# RaspiPowerHat.net
KiCad netlist of a schematic drawn in EAGLE
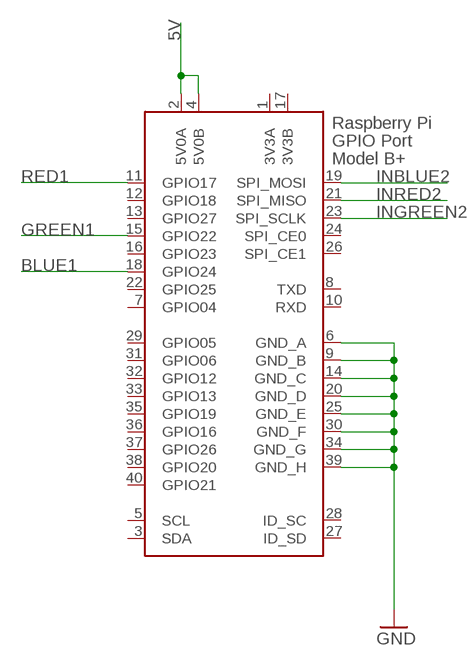
[diagram p0: schematic, sheet 1]
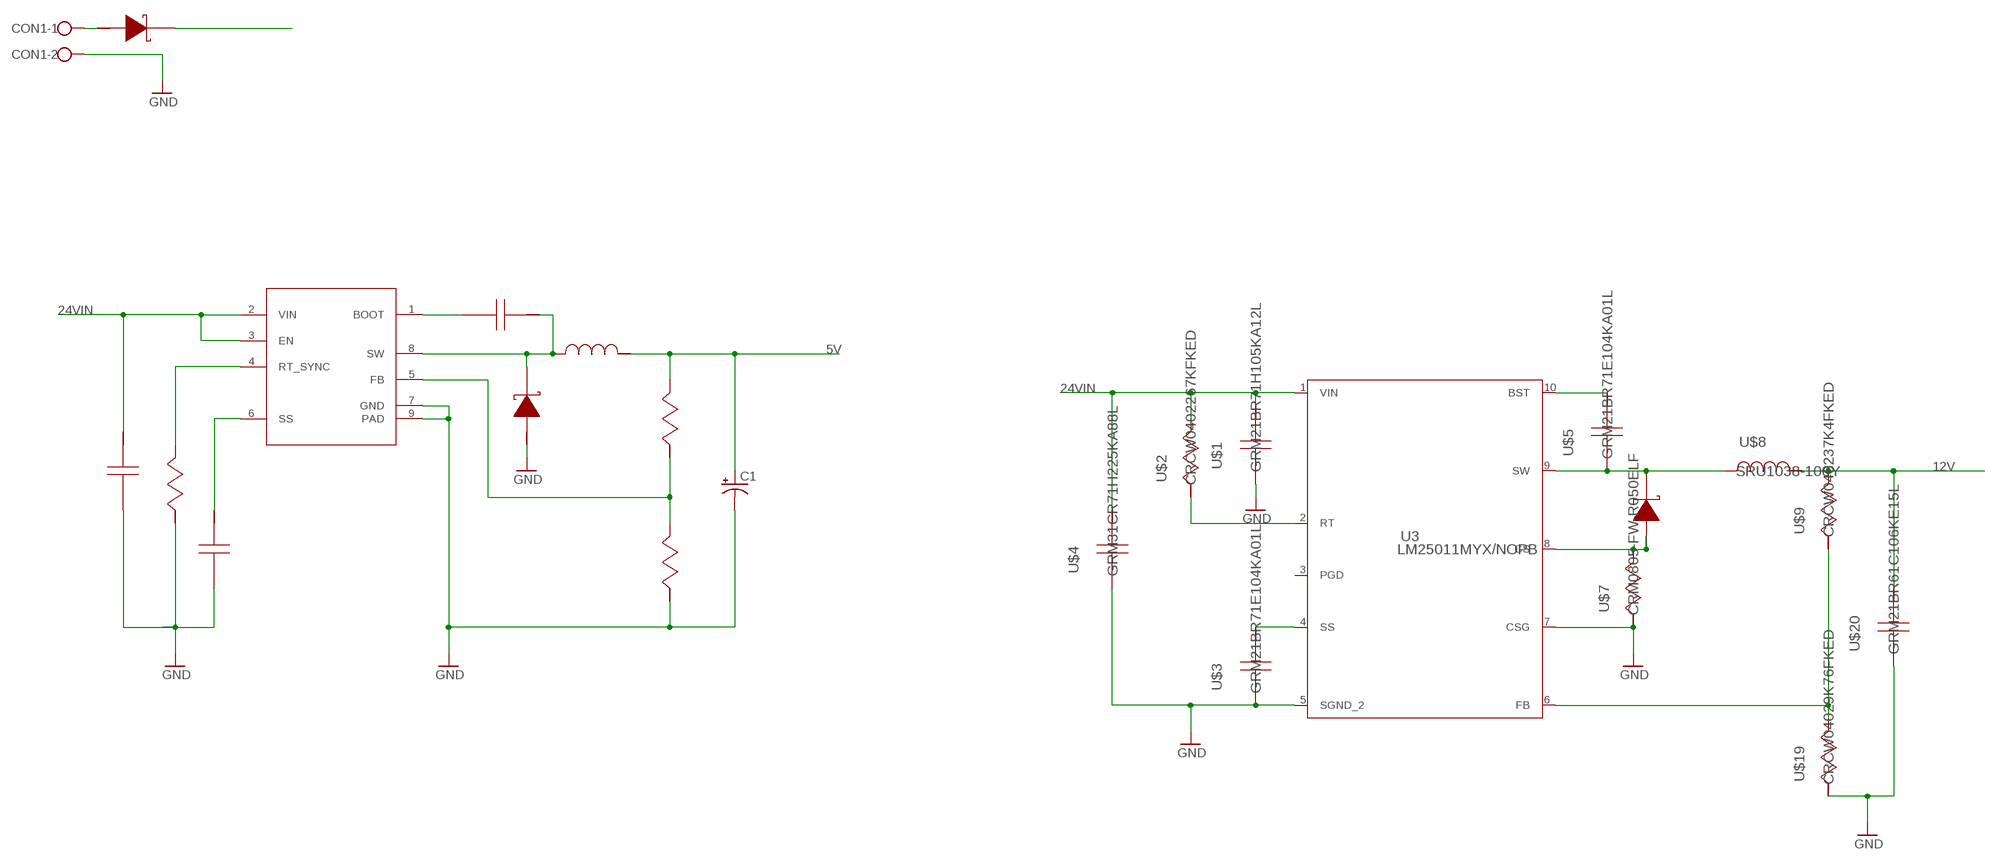
[diagram p1: schematic, sheet 2]
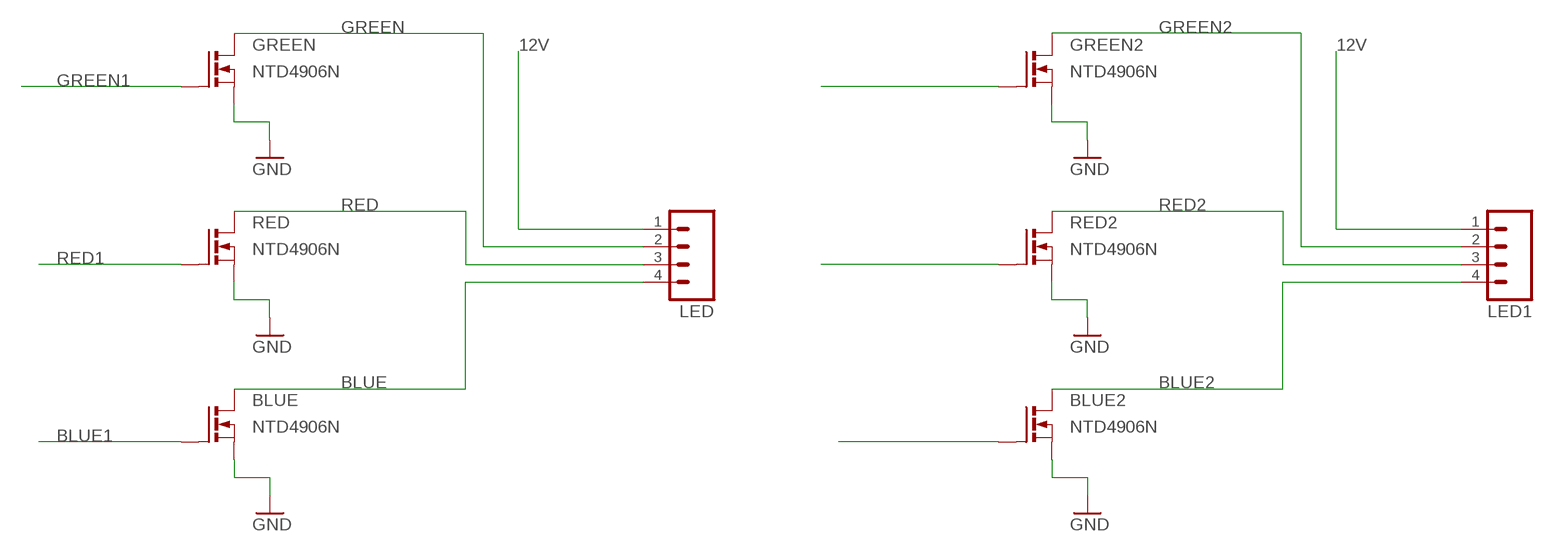
[diagram p2: schematic, sheet 3]

(export (version "E")
  (design (tool "Eeschema 10.0.6"))
  (components
    (comp (ref "C1")
      (value "CPOL-USC")
      (footprint "eagle-import:PANASONIC_C")
      (libsource (lib "eagle-import") (part "CPOL-USC"))
    )
    (comp (ref "CON1")
      (value "W237-102")
      (footprint "eagle-import:W237-102")
      (fields (field (name "MPN") "237-102"))
      (libsource (lib "eagle-import") (part "W237-102"))
    )
    (comp (ref "U$1")
      (value "GRM21BR71H105KA12L")
      (footprint "eagle-import:0805")
      (libsource (lib "eagle-import") (part "GRM21BR71H105KA12L"))
    )
    (comp (ref "U$2")
      (value "CRCW0402267KFKED")
      (footprint "eagle-import:0402")
      (fields (field (name "POWER") "0.063") (field (name "TOLERANCE") "1.0"))
      (libsource (lib "eagle-import") (part "CRCW0402267KFKED"))
    )
    (comp (ref "U$3")
      (value "GRM21BR71E104KA01L")
      (footprint "eagle-import:0805")
      (libsource (lib "eagle-import") (part "GRM21BR71E104KA01L"))
    )
    (comp (ref "U$4")
      (value "GRM31CR71H225KA88L")
      (footprint "eagle-import:1206_190")
      (libsource (lib "eagle-import") (part "TILM25011_GRM31CR71H225KA88L"))
    )
    (comp (ref "U$5")
      (value "GRM21BR71E104KA01L")
      (footprint "eagle-import:0805")
      (libsource (lib "eagle-import") (part "GRM21BR71E104KA01L"))
    )
    (comp (ref "U$6")
      (value "B360A-13-F")
      (footprint "eagle-import:SMA")
      (libsource (lib "eagle-import") (part "B360A-13-F"))
    )
    (comp (ref "U$7")
      (value "CRM0805-FW-R050ELF")
      (footprint "eagle-import:0805")
      (fields (field (name "POWER") "0.25") (field (name "TOLERANCE") "1.0"))
      (libsource (lib "eagle-import") (part "CRM0805-FW-R050ELF"))
    )
    (comp (ref "U$8")
      (value "SRU1038-100Y")
      (footprint "eagle-import:SRU1038")
      (libsource (lib "eagle-import") (part "SRU1038-100Y"))
    )
    (comp (ref "U$9")
      (value "CRCW040237K4FKED")
      (footprint "eagle-import:0402")
      (fields (field (name "POWER") "0.063") (field (name "TOLERANCE") "1.0"))
      (libsource (lib "eagle-import") (part "CRCW040237K4FKED"))
    )
    (comp (ref "U$10")
      (value "C0805C104K5RACTU")
      (footprint "eagle-import:0805")
      (libsource (lib "eagle-import") (part "C0805C104K5RACTU"))
    )
    (comp (ref "U$11")
      (value "VLP8040T-6R8M")
      (footprint "eagle-import:VLP8040")
      (fields (field (name "MANUFACTURER") "TDK"))
      (libsource (lib "eagle-import") (part "VLP8040T-6R8M"))
    )
    (comp (ref "U$12")
      (value "B360A-13-F")
      (footprint "eagle-import:SMA")
      (libsource (lib "eagle-import") (part "B360A-13-F"))
    )
    (comp (ref "U$13")
      (value "RC0603FR-0768KL")
      (footprint "eagle-import:0603")
      (fields (field (name "POWER") "0.1") (field (name "TOLERANCE") "1.0"))
      (libsource (lib "eagle-import") (part "RC0603FR-0768KL"))
    )
    (comp (ref "U$14")
      (value "RC0603FR-0712KL")
      (footprint "eagle-import:0603")
      (fields (field (name "POWER") "0.1") (field (name "TOLERANCE") "1.0"))
      (libsource (lib "eagle-import") (part "RC0603FR-0712KL"))
    )
    (comp (ref "U$15")
      (value "B360A-13-F")
      (footprint "eagle-import:SMA")
      (libsource (lib "eagle-import") (part "B360A-13-F"))
    )
    (comp (ref "U$16")
      (value "GRM155R71C822KA01D")
      (footprint "eagle-import:0402")
      (libsource (lib "eagle-import") (part "GRM155R71C822KA01D"))
    )
    (comp (ref "U$17")
      (value "CRCW040224K3FKED")
      (footprint "eagle-import:0402")
      (fields (field (name "POWER") "0.063") (field (name "TOLERANCE") "1.0"))
      (libsource (lib "eagle-import") (part "CRCW040224K3FKED"))
    )
    (comp (ref "U$18")
      (value "GRM31CR71H225KA88L")
      (footprint "eagle-import:1206_190")
      (libsource (lib "eagle-import") (part "GRM31CR71H225KA88L"))
    )
    (comp (ref "U$19")
      (value "CRCW04029K76FKED")
      (footprint "eagle-import:0402")
      (fields (field (name "POWER") "0.063") (field (name "TOLERANCE") "1.0"))
      (libsource (lib "eagle-import") (part "CRCW04029K76FKED"))
    )
    (comp (ref "U$20")
      (value "GRM21BR61C106KE15L")
      (footprint "eagle-import:0805")
      (libsource (lib "eagle-import") (part "GRM21BR61C106KE15L"))
    )
    (comp (ref "U2")
      (value "Value")
      (footprint "eagle-import:DDA0008E_N")
      (fields
        (field (name "ALTERNATEPARTNUMBER") "LMR14050SDDA")
        (field (name "MANUFACTURER") "Texas Instruments")
        (field (name "MANUFACTURER_PART_NUMBER") "LMR14050SDDAR")
      )
      (libsource (lib "eagle-import") (part "LMR14050SDDAR"))
    )
    (comp (ref "U3")
      (value "LM25011MYX/NOPB")
      (footprint "eagle-import:MUC10A")
      (libsource (lib "eagle-import") (part "LM25011MYX/NOPB"))
    )
    (comp (ref "BLUE")
      (value "NTD4906N")
      (footprint "eagle-import:D-PAK_TO252AA")
      (libsource (lib "eagle-import") (part "4906N"))
    )
    (comp (ref "BLUE2")
      (value "NTD4906N")
      (footprint "eagle-import:D-PAK_TO252AA")
      (libsource (lib "eagle-import") (part "4906N"))
    )
    (comp (ref "GREEN")
      (value "NTD4906N")
      (footprint "eagle-import:D-PAK_TO252AA")
      (libsource (lib "eagle-import") (part "4906N"))
    )
    (comp (ref "GREEN2")
      (value "NTD4906N")
      (footprint "eagle-import:D-PAK_TO252AA")
      (libsource (lib "eagle-import") (part "4906N"))
    )
    (comp (ref "LED")
      (value "M04JST-PTH-VERT")
      (footprint "eagle-import:JST-4-PTH-VERT")
      (libsource (lib "eagle-import") (part "M04JST-PTH-VERT"))
    )
    (comp (ref "LED1")
      (value "M04JST-PTH-VERT")
      (footprint "eagle-import:JST-4-PTH-VERT")
      (libsource (lib "eagle-import") (part "M04JST-PTH-VERT"))
    )
    (comp (ref "RED")
      (value "NTD4906N")
      (footprint "eagle-import:D-PAK_TO252AA")
      (libsource (lib "eagle-import") (part "4906N"))
    )
    (comp (ref "RED2")
      (value "NTD4906N")
      (footprint "eagle-import:D-PAK_TO252AA")
      (libsource (lib "eagle-import") (part "4906N"))
    )
    (comp (ref "X1")
      (value "RASPI_GPIO_B+#_PIN")
      (footprint "eagle-import:RASPI_GPIO_B+_PIN")
      (libsource (lib "eagle-import") (part "RASPI_GPIO_B+#_PIN"))
    )
  )
  (nets
    (net (code "1") (name "3V3A") (class "Default")
      (node (ref "X1") (pin "1") (pinfunction "3V3A_1") (pintype "power_in"))
    )
    (net (code "2") (name "3V3B") (class "Default")
      (node (ref "X1") (pin "17") (pinfunction "3V3B_17") (pintype "power_in"))
    )
    (net (code "3") (name "5V") (class "Default")
      (node (ref "C1") (pin "+") (pinfunction "+_+") (pintype "passive"))
      (node (ref "U$11") (pin "2") (pinfunction "2_2") (pintype "passive"))
      (node (ref "U$13") (pin "1") (pinfunction "1_1") (pintype "passive"))
      (node (ref "X1") (pin "2") (pinfunction "5V0A_2") (pintype "power_in"))
      (node (ref "X1") (pin "4") (pinfunction "5V0B_4") (pintype "power_in"))
    )
    (net (code "4") (name "12V") (class "Default")
      (node (ref "LED") (pin "1") (pinfunction "1_1") (pintype "passive"))
      (node (ref "LED1") (pin "1") (pinfunction "1_1") (pintype "passive"))
      (node (ref "U$20") (pin "1") (pinfunction "1_1") (pintype "passive"))
      (node (ref "U$8") (pin "2") (pinfunction "2_2") (pintype "passive"))
      (node (ref "U$9") (pin "1") (pinfunction "1_1") (pintype "passive"))
    )
    (net (code "5") (name "24VIN") (class "Default")
      (node (ref "U$1") (pin "1") (pinfunction "1_1") (pintype "passive"))
      (node (ref "U$15") (pin "1") (pinfunction "K_1") (pintype "passive"))
      (node (ref "U$18") (pin "1") (pinfunction "1_1") (pintype "passive"))
      (node (ref "U$2") (pin "1") (pinfunction "1_1") (pintype "passive"))
      (node (ref "U$4") (pin "1") (pinfunction "1_1") (pintype "passive"))
      (node (ref "U2") (pin "2") (pinfunction "VIN_2") (pintype "power_in"))
      (node (ref "U2") (pin "3") (pinfunction "EN_3") (pintype "input"))
      (node (ref "U3") (pin "1") (pinfunction "VIN_1") (pintype "passive"))
    )
    (net (code "6") (name "BLUE") (class "Default")
      (node (ref "BLUE") (pin "4") (pinfunction "D_4") (pintype "passive"))
      (node (ref "LED") (pin "4") (pinfunction "4_4") (pintype "passive"))
    )
    (net (code "7") (name "BLUE1") (class "Default")
      (node (ref "BLUE") (pin "1") (pinfunction "G_1") (pintype "passive"))
      (node (ref "X1") (pin "18") (pinfunction "GPIO24_18") (pintype "bidirectional"))
    )
    (net (code "8") (name "BLUE2") (class "Default")
      (node (ref "BLUE2") (pin "4") (pinfunction "D_4") (pintype "passive"))
      (node (ref "LED1") (pin "4") (pinfunction "4_4") (pintype "passive"))
    )
    (net (code "9") (name "GND") (class "Default")
      (node (ref "BLUE") (pin "3") (pinfunction "SG1_3") (pintype "passive"))
      (node (ref "BLUE2") (pin "3") (pinfunction "SG1_3") (pintype "passive"))
      (node (ref "C1") (pin "-") (pinfunction "-_-") (pintype "passive"))
      (node (ref "CON1") (pin "2") (pinfunction "KL_2") (pintype "passive"))
      (node (ref "GREEN") (pin "3") (pinfunction "SG1_3") (pintype "passive"))
      (node (ref "GREEN2") (pin "3") (pinfunction "SG1_3") (pintype "passive"))
      (node (ref "RED") (pin "3") (pinfunction "SG1_3") (pintype "passive"))
      (node (ref "RED2") (pin "3") (pinfunction "SG1_3") (pintype "passive"))
      (node (ref "U$1") (pin "2") (pinfunction "2_2") (pintype "passive"))
      (node (ref "U$12") (pin "2") (pinfunction "A_2") (pintype "passive"))
      (node (ref "U$14") (pin "2") (pinfunction "2_2") (pintype "passive"))
      (node (ref "U$16") (pin "2") (pinfunction "2_2") (pintype "passive"))
      (node (ref "U$17") (pin "2") (pinfunction "2_2") (pintype "passive"))
      (node (ref "U$18") (pin "2") (pinfunction "2_2") (pintype "passive"))
      (node (ref "U$19") (pin "2") (pinfunction "2_2") (pintype "passive"))
      (node (ref "U$20") (pin "2") (pinfunction "2_2") (pintype "passive"))
      (node (ref "U$3") (pin "2") (pinfunction "2_2") (pintype "passive"))
      (node (ref "U$4") (pin "2") (pinfunction "2_2") (pintype "passive"))
      (node (ref "U$7") (pin "2") (pinfunction "2_2") (pintype "passive"))
      (node (ref "U2") (pin "7") (pinfunction "GND_7") (pintype "power_in"))
      (node (ref "U2") (pin "9") (pinfunction "PAD_9") (pintype "power_in"))
      (node (ref "U3") (pin "5") (pinfunction "SGND_2_5") (pintype "passive"))
      (node (ref "U3") (pin "7") (pinfunction "CSG_7") (pintype "passive"))
      (node (ref "X1") (pin "14") (pinfunction "GND_C_14") (pintype "power_in"))
      (node (ref "X1") (pin "20") (pinfunction "GND_D_20") (pintype "power_in"))
      (node (ref "X1") (pin "25") (pinfunction "GND_E_25") (pintype "power_in"))
      (node (ref "X1") (pin "30") (pinfunction "GND_F_30") (pintype "power_in"))
      (node (ref "X1") (pin "34") (pinfunction "GND_G_34") (pintype "power_in"))
      (node (ref "X1") (pin "39") (pinfunction "GND_H_39") (pintype "power_in"))
      (node (ref "X1") (pin "6") (pinfunction "GND_A_6") (pintype "power_in"))
      (node (ref "X1") (pin "9") (pinfunction "GND_B_9") (pintype "power_in"))
    )
    (net (code "10") (name "GREEN") (class "Default")
      (node (ref "GREEN") (pin "4") (pinfunction "D_4") (pintype "passive"))
      (node (ref "LED") (pin "2") (pinfunction "2_2") (pintype "passive"))
    )
    (net (code "11") (name "GREEN1") (class "Default")
      (node (ref "GREEN") (pin "1") (pinfunction "G_1") (pintype "passive"))
      (node (ref "X1") (pin "15") (pinfunction "GPIO22_15") (pintype "bidirectional"))
    )
    (net (code "12") (name "GREEN2") (class "Default")
      (node (ref "GREEN2") (pin "4") (pinfunction "D_4") (pintype "passive"))
      (node (ref "LED1") (pin "2") (pinfunction "2_2") (pintype "passive"))
    )
    (net (code "13") (name "INBLUE2") (class "Default")
      (node (ref "BLUE2") (pin "1") (pinfunction "G_1") (pintype "passive"))
      (node (ref "X1") (pin "19") (pinfunction "SPI_MOSI_19") (pintype "bidirectional"))
    )
    (net (code "14") (name "INGREEN2") (class "Default")
      (node (ref "GREEN2") (pin "1") (pinfunction "G_1") (pintype "passive"))
      (node (ref "X1") (pin "23") (pinfunction "SPI_SCLK_23") (pintype "bidirectional"))
    )
    (net (code "15") (name "INRED2") (class "Default")
      (node (ref "RED2") (pin "1") (pinfunction "G_1") (pintype "passive"))
      (node (ref "X1") (pin "21") (pinfunction "SPI_MISO_21") (pintype "bidirectional"))
    )
    (net (code "16") (name "Net-(CON1A-KL)") (class "Default")
      (node (ref "CON1") (pin "1") (pinfunction "KL_1") (pintype "passive"))
      (node (ref "U$15") (pin "2") (pinfunction "A_2") (pintype "passive"))
    )
    (net (code "17") (name "Net-(U$6-A)") (class "Default")
      (node (ref "U$6") (pin "2") (pinfunction "A_2") (pintype "passive"))
      (node (ref "U$7") (pin "1") (pinfunction "1_1") (pintype "passive"))
      (node (ref "U3") (pin "8") (pinfunction "CS_8") (pintype "passive"))
    )
    (net (code "18") (name "Net-(U$6-K)") (class "Default")
      (node (ref "U$5") (pin "2") (pinfunction "2_2") (pintype "passive"))
      (node (ref "U$6") (pin "1") (pinfunction "K_1") (pintype "passive"))
      (node (ref "U$8") (pin "1") (pinfunction "1_1") (pintype "passive"))
      (node (ref "U3") (pin "9") (pinfunction "SW_9") (pintype "passive"))
    )
    (net (code "19") (name "Net-(U$12-K)") (class "Default")
      (node (ref "U$10") (pin "1") (pinfunction "1_1") (pintype "passive"))
      (node (ref "U$11") (pin "1") (pinfunction "1_1") (pintype "passive"))
      (node (ref "U$12") (pin "1") (pinfunction "K_1") (pintype "passive"))
      (node (ref "U2") (pin "8") (pinfunction "SW_8") (pintype "power_in"))
    )
    (net (code "20") (name "Net-(U2-BOOT)") (class "Default")
      (node (ref "U$10") (pin "2") (pinfunction "2_2") (pintype "passive"))
      (node (ref "U2") (pin "1") (pinfunction "BOOT_1") (pintype "passive"))
    )
    (net (code "21") (name "Net-(U2-FB)") (class "Default")
      (node (ref "U$13") (pin "2") (pinfunction "2_2") (pintype "passive"))
      (node (ref "U$14") (pin "1") (pinfunction "1_1") (pintype "passive"))
      (node (ref "U2") (pin "5") (pinfunction "FB_5") (pintype "input"))
    )
    (net (code "22") (name "Net-(U2-RT_SYNC)") (class "Default")
      (node (ref "U$17") (pin "1") (pinfunction "1_1") (pintype "passive"))
      (node (ref "U2") (pin "4") (pinfunction "RT_SYNC_4") (pintype "passive"))
    )
    (net (code "23") (name "Net-(U2-SS)") (class "Default")
      (node (ref "U$16") (pin "1") (pinfunction "1_1") (pintype "passive"))
      (node (ref "U2") (pin "6") (pinfunction "SS_6") (pintype "input"))
    )
    (net (code "24") (name "Net-(U3-BST)") (class "Default")
      (node (ref "U$5") (pin "1") (pinfunction "1_1") (pintype "passive"))
      (node (ref "U3") (pin "10") (pinfunction "BST_10") (pintype "passive"))
    )
    (net (code "25") (name "Net-(U3-FB)") (class "Default")
      (node (ref "U$19") (pin "1") (pinfunction "1_1") (pintype "passive"))
      (node (ref "U$9") (pin "2") (pinfunction "2_2") (pintype "passive"))
      (node (ref "U3") (pin "6") (pinfunction "FB_6") (pintype "passive"))
    )
    (net (code "26") (name "Net-(U3-RT)") (class "Default")
      (node (ref "U$2") (pin "2") (pinfunction "2_2") (pintype "passive"))
      (node (ref "U3") (pin "2") (pinfunction "RT_2") (pintype "passive"))
    )
    (net (code "27") (name "Net-(U3-SS)") (class "Default")
      (node (ref "U$3") (pin "1") (pinfunction "1_1") (pintype "passive"))
      (node (ref "U3") (pin "4") (pinfunction "SS_4") (pintype "passive"))
    )
    (net (code "28") (name "RED") (class "Default")
      (node (ref "LED") (pin "3") (pinfunction "3_3") (pintype "passive"))
      (node (ref "RED") (pin "4") (pinfunction "D_4") (pintype "passive"))
    )
    (net (code "29") (name "RED1") (class "Default")
      (node (ref "RED") (pin "1") (pinfunction "G_1") (pintype "passive"))
      (node (ref "X1") (pin "11") (pinfunction "GPIO17_11") (pintype "bidirectional"))
    )
    (net (code "30") (name "RED2") (class "Default")
      (node (ref "LED1") (pin "3") (pinfunction "3_3") (pintype "passive"))
      (node (ref "RED2") (pin "4") (pinfunction "D_4") (pintype "passive"))
    )
    (net (code "31") (name "unconnected-(U3-PGD-Pad3)") (class "Default")
      (node (ref "U3") (pin "3") (pinfunction "PGD_3") (pintype "passive"))
    )
    (net (code "32") (name "unconnected-(X1-GPIO04-Pad7)") (class "Default")
      (node (ref "X1") (pin "7") (pinfunction "GPIO04_7") (pintype "bidirectional"))
    )
    (net (code "33") (name "unconnected-(X1-GPIO05-Pad29)") (class "Default")
      (node (ref "X1") (pin "29") (pinfunction "GPIO05_29") (pintype "no_connect"))
    )
    (net (code "34") (name "unconnected-(X1-GPIO06-Pad31)") (class "Default")
      (node (ref "X1") (pin "31") (pinfunction "GPIO06_31") (pintype "no_connect"))
    )
    (net (code "35") (name "unconnected-(X1-GPIO12-Pad32)") (class "Default")
      (node (ref "X1") (pin "32") (pinfunction "GPIO12_32") (pintype "no_connect"))
    )
    (net (code "36") (name "unconnected-(X1-GPIO13-Pad33)") (class "Default")
      (node (ref "X1") (pin "33") (pinfunction "GPIO13_33") (pintype "no_connect"))
    )
    (net (code "37") (name "unconnected-(X1-GPIO16-Pad36)") (class "Default")
      (node (ref "X1") (pin "36") (pinfunction "GPIO16_36") (pintype "no_connect"))
    )
    (net (code "38") (name "unconnected-(X1-GPIO18-Pad12)") (class "Default")
      (node (ref "X1") (pin "12") (pinfunction "GPIO18_12") (pintype "bidirectional"))
    )
    (net (code "39") (name "unconnected-(X1-GPIO19-Pad35)") (class "Default")
      (node (ref "X1") (pin "35") (pinfunction "GPIO19_35") (pintype "no_connect"))
    )
    (net (code "40") (name "unconnected-(X1-GPIO20-Pad38)") (class "Default")
      (node (ref "X1") (pin "38") (pinfunction "GPIO20_38") (pintype "no_connect"))
    )
    (net (code "41") (name "unconnected-(X1-GPIO21-Pad40)") (class "Default")
      (node (ref "X1") (pin "40") (pinfunction "GPIO21_40") (pintype "no_connect"))
    )
    (net (code "42") (name "unconnected-(X1-GPIO23-Pad16)") (class "Default")
      (node (ref "X1") (pin "16") (pinfunction "GPIO23_16") (pintype "bidirectional"))
    )
    (net (code "43") (name "unconnected-(X1-GPIO25-Pad22)") (class "Default")
      (node (ref "X1") (pin "22") (pinfunction "GPIO25_22") (pintype "bidirectional"))
    )
    (net (code "44") (name "unconnected-(X1-GPIO26-Pad37)") (class "Default")
      (node (ref "X1") (pin "37") (pinfunction "GPIO26_37") (pintype "no_connect"))
    )
    (net (code "45") (name "unconnected-(X1-GPIO27-Pad13)") (class "Default")
      (node (ref "X1") (pin "13") (pinfunction "GPIO27_13") (pintype "bidirectional"))
    )
    (net (code "46") (name "unconnected-(X1-ID_SC-Pad28)") (class "Default")
      (node (ref "X1") (pin "28") (pinfunction "ID_SC_28") (pintype "no_connect"))
    )
    (net (code "47") (name "unconnected-(X1-ID_SD-Pad27)") (class "Default")
      (node (ref "X1") (pin "27") (pinfunction "ID_SD_27") (pintype "no_connect"))
    )
    (net (code "48") (name "unconnected-(X1-RXD-Pad10)") (class "Default")
      (node (ref "X1") (pin "10") (pinfunction "RXD_10") (pintype "bidirectional"))
    )
    (net (code "49") (name "unconnected-(X1-SCL-Pad5)") (class "Default")
      (node (ref "X1") (pin "5") (pinfunction "SCL_5") (pintype "bidirectional"))
    )
    (net (code "50") (name "unconnected-(X1-SDA-Pad3)") (class "Default")
      (node (ref "X1") (pin "3") (pinfunction "SDA_3") (pintype "bidirectional"))
    )
    (net (code "51") (name "unconnected-(X1-SPI_CE0-Pad24)") (class "Default")
      (node (ref "X1") (pin "24") (pinfunction "SPI_CE0_24") (pintype "bidirectional"))
    )
    (net (code "52") (name "unconnected-(X1-SPI_CE1-Pad26)") (class "Default")
      (node (ref "X1") (pin "26") (pinfunction "SPI_CE1_26") (pintype "bidirectional"))
    )
    (net (code "53") (name "unconnected-(X1-TXD-Pad8)") (class "Default")
      (node (ref "X1") (pin "8") (pinfunction "TXD_8") (pintype "bidirectional"))
    )
  )
)
